# 2_PowerPerif.net
KiCad netlist of a schematic drawn in Altium Designer
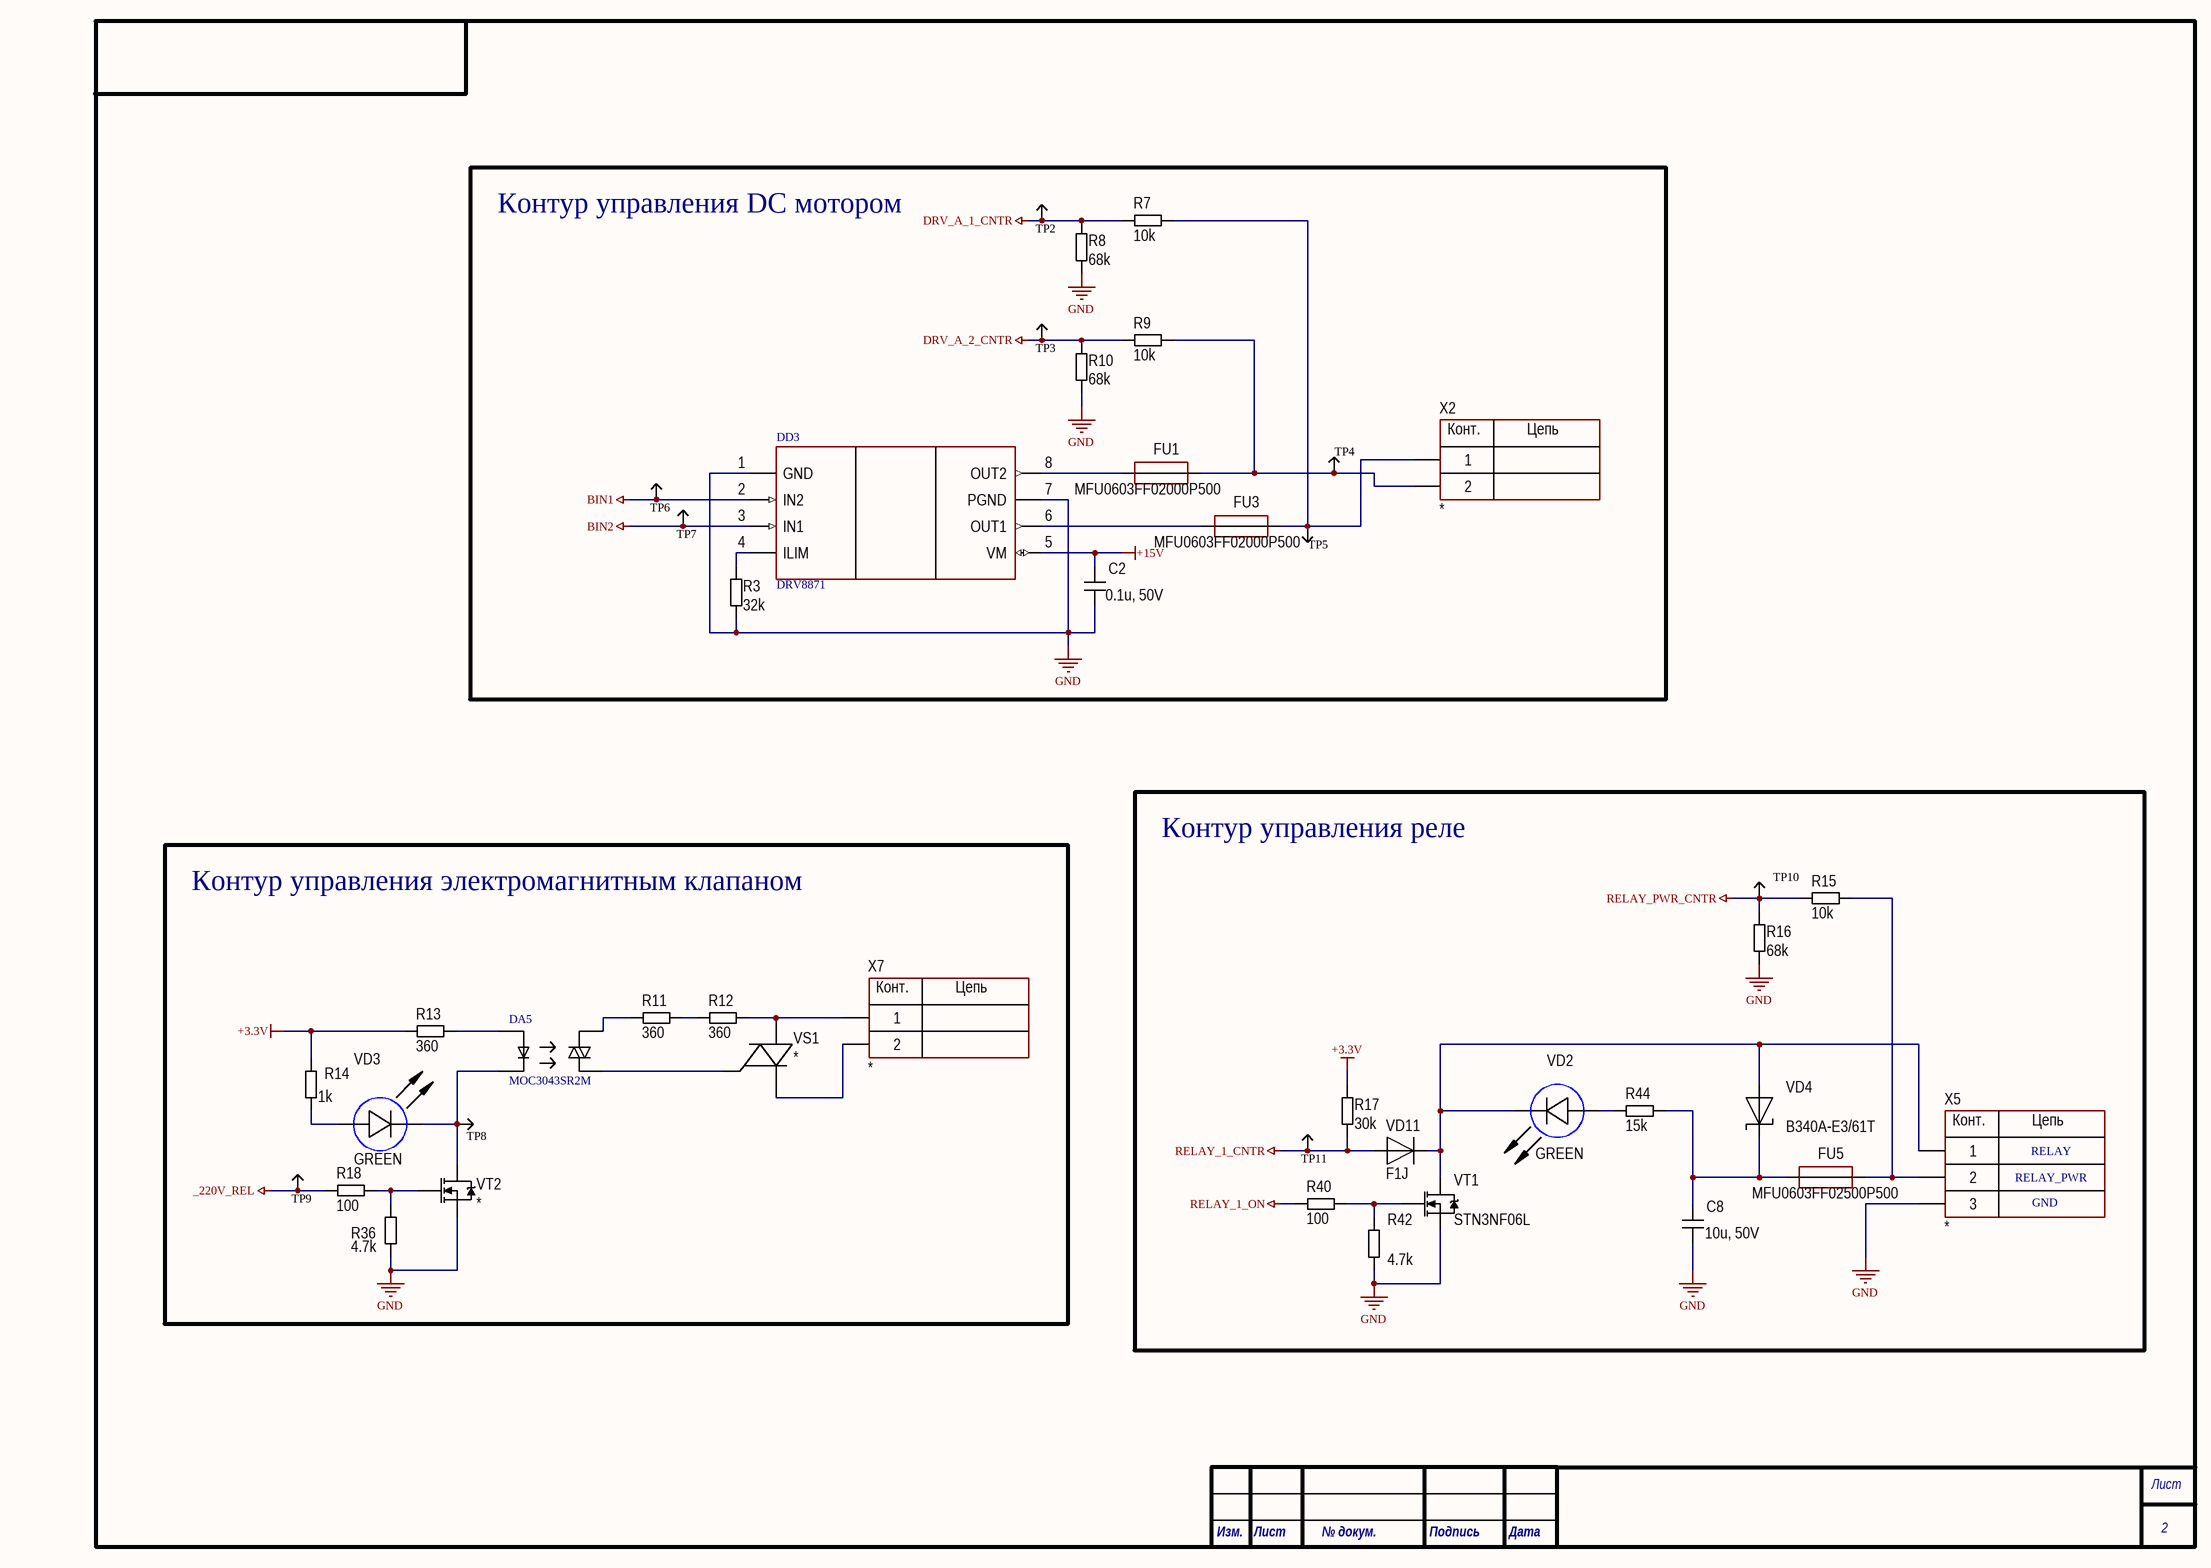
[diagram p0: 2_PowerPerif.SchDoc]

(export (version "E")
  (design (tool "Eeschema 10.0.6"))
  (components
    (comp (ref "C2")
      (value "0.1u, 50V")
      (footprint "CH0402C")
      (libsource (lib "Condensators") (part "Capacitor"))
    )
    (comp (ref "C8")
      (value "10u, 50V")
      (footprint "CH1206C")
      (libsource (lib "Condensators") (part "Capacitor"))
    )
    (comp (ref "DA5") (value "MOC3043SR2M") (footprint "DIP6") (libsource (lib "MicroIC") (part "MOC3063")))
    (comp (ref "DD3") (value "DRV8871") (footprint "8-HSOP") (libsource (lib "MicroIC") (part "DRV8871")))
    (comp (ref "FU1")
      (value "MFU0603FF02000P500")
      (footprint "CH0603F")
      (libsource (lib "Melochi") (part "Fuse"))
    )
    (comp (ref "FU3")
      (value "MFU0603FF02000P500")
      (footprint "CH0603F")
      (libsource (lib "Melochi") (part "Fuse"))
    )
    (comp (ref "FU5")
      (value "MFU0603FF02500P500")
      (footprint "CH0603F")
      (libsource (lib "Melochi") (part "Fuse"))
    )
    (comp (ref "R3") (value "32k") (footprint "CH0603R") (libsource (lib "Resistors") (part "Resistor")))
    (comp (ref "R7") (value "10k") (footprint "CH0402R") (libsource (lib "Resistors") (part "Resistor")))
    (comp (ref "R8") (value "68k") (footprint "CH0402R") (libsource (lib "Resistors") (part "Resistor")))
    (comp (ref "R9") (value "10k") (footprint "CH0402R") (libsource (lib "Resistors") (part "Resistor")))
    (comp (ref "R10") (value "68k") (footprint "CH0402R") (libsource (lib "Resistors") (part "Resistor")))
    (comp (ref "R11") (value "360") (footprint "CH1206R") (libsource (lib "Resistors") (part "Resistor")))
    (comp (ref "R12") (value "360") (footprint "CH1206R") (libsource (lib "Resistors") (part "Resistor")))
    (comp (ref "R13") (value "360") (footprint "CH0805R") (libsource (lib "Resistors") (part "Resistor")))
    (comp (ref "R14") (value "1k") (footprint "CH0805R") (libsource (lib "Resistors") (part "Resistor")))
    (comp (ref "R15") (value "10k") (footprint "CH0402R") (libsource (lib "Resistors") (part "Resistor")))
    (comp (ref "R16") (value "68k") (footprint "CH0402R") (libsource (lib "Resistors") (part "Resistor")))
    (comp (ref "R17") (value "30k") (footprint "CH0402R") (libsource (lib "Resistors") (part "Resistor")))
    (comp (ref "R18") (value "100") (footprint "CH0805R") (libsource (lib "Resistors") (part "Resistor")))
    (comp (ref "R36") (value "4.7k") (footprint "CH0402R") (libsource (lib "Resistors") (part "Resistor")))
    (comp (ref "R40") (value "100") (footprint "CH0805R") (libsource (lib "Resistors") (part "Resistor")))
    (comp (ref "R42") (value "4.7k") (footprint "CH0402R") (libsource (lib "Resistors") (part "Resistor")))
    (comp (ref "R44") (value "15k") (footprint "CH0805R") (libsource (lib "Resistors") (part "Resistor")))
    (comp (ref "TP2") (value "~") (footprint "TestPoint") (libsource (lib "Melochi") (part "TestPoint")))
    (comp (ref "TP3") (value "~") (footprint "TestPoint") (libsource (lib "Melochi") (part "TestPoint")))
    (comp (ref "TP4") (value "~") (footprint "TestPoint") (libsource (lib "Melochi") (part "TestPoint")))
    (comp (ref "TP5") (value "~") (footprint "TestPoint") (libsource (lib "Melochi") (part "TestPoint")))
    (comp (ref "TP6") (value "~") (footprint "TestPoint") (libsource (lib "Melochi") (part "TestPoint")))
    (comp (ref "TP7") (value "~") (footprint "TestPoint") (libsource (lib "Melochi") (part "TestPoint")))
    (comp (ref "TP8") (value "~") (footprint "TestPoint") (libsource (lib "Melochi") (part "TestPoint")))
    (comp (ref "TP9") (value "~") (footprint "TestPoint") (libsource (lib "Melochi") (part "TestPoint")))
    (comp (ref "TP10") (value "~") (footprint "TestPoint") (libsource (lib "Melochi") (part "TestPoint")))
    (comp (ref "TP11") (value "~") (footprint "TestPoint") (libsource (lib "Melochi") (part "TestPoint")))
    (comp (ref "VD2") (value "GREEN") (footprint "CH0603LB") (libsource (lib "Diods") (part "LED_1")))
    (comp (ref "VD3") (value "GREEN") (footprint "CH0603LB") (libsource (lib "Diods") (part "LED_1")))
    (comp (ref "VD4")
      (value "B340A-E3/61T")
      (footprint "SMA")
      (libsource (lib "Diods") (part "Diod Schottky"))
    )
    (comp (ref "VD11") (value "F1J") (footprint "SOD123F") (libsource (lib "Diods") (part "Diod")))
    (comp (ref "VS1")
      (value "*")
      (footprint "SOT223_G-D-S")
      (description "Bipolar")
      (libsource (lib "Tranzistor") (part "TRIAC"))
    )
    (comp (ref "VT1")
      (value "STN3NF06L")
      (footprint "SOT223_G-D-S")
      (description "Mosfet")
      (libsource (lib "Tranzistor") (part "N-chanel"))
    )
    (comp (ref "VT2")
      (value "*")
      (footprint "SOT23_123")
      (description "Mosfet")
      (libsource (lib "Tranzistor") (part "N-chanel"))
    )
    (comp (ref "X2")
      (value "*")
      (footprint "CON: MX-22-05-3021")
      (libsource (lib "Connectors") (part "2-Connector"))
    )
    (comp (ref "X5")
      (value "*")
      (footprint "CON: 300-03P-5.0")
      (libsource (lib "Connectors") (part "3-Connector"))
    )
    (comp (ref "X7")
      (value "*")
      (footprint "CON: 300-02P-5.0")
      (libsource (lib "Connectors") (part "2-Connector"))
    )
  )
  (nets
    (net (code "1") (name "+3.3V") (class "Default")
      (node (ref "R13") (pin "2") (pinfunction "2_2") (pintype "passive"))
      (node (ref "R14") (pin "2") (pinfunction "2_2") (pintype "passive"))
      (node (ref "R17") (pin "2") (pinfunction "2_2") (pintype "passive"))
    )
    (net (code "2") (name "+15V") (class "Default")
      (node (ref "C2") (pin "2") (pinfunction "2_2") (pintype "passive"))
      (node (ref "DD3") (pin "5") (pinfunction "VM_5") (pintype "bidirectional"))
    )
    (net (code "3") (name "BIN1") (class "Default")
      (node (ref "DD3") (pin "2") (pinfunction "IN2_2") (pintype "input"))
      (node (ref "TP6") (pin "0") (pinfunction "0_0") (pintype "passive"))
    )
    (net (code "4") (name "BIN2") (class "Default")
      (node (ref "DD3") (pin "3") (pinfunction "IN1_3") (pintype "input"))
      (node (ref "TP7") (pin "0") (pinfunction "0_0") (pintype "passive"))
    )
    (net (code "5") (name "DRV_A_1_CNTR") (class "Default")
      (node (ref "R7") (pin "1") (pinfunction "1_1") (pintype "passive"))
      (node (ref "R8") (pin "2") (pinfunction "2_2") (pintype "passive"))
      (node (ref "TP2") (pin "0") (pinfunction "0_0") (pintype "passive"))
    )
    (net (code "6") (name "DRV_A_2_CNTR") (class "Default")
      (node (ref "R10") (pin "2") (pinfunction "2_2") (pintype "passive"))
      (node (ref "R9") (pin "1") (pinfunction "1_1") (pintype "passive"))
      (node (ref "TP3") (pin "0") (pinfunction "0_0") (pintype "passive"))
    )
    (net (code "7") (name "GND") (class "Default")
      (node (ref "C2") (pin "1") (pinfunction "1_1") (pintype "passive"))
      (node (ref "C8") (pin "1") (pinfunction "1_1") (pintype "passive"))
      (node (ref "DD3") (pin "1") (pinfunction "GND_1") (pintype "power_in"))
      (node (ref "DD3") (pin "7") (pinfunction "PGND_7") (pintype "power_in"))
      (node (ref "R10") (pin "1") (pinfunction "1_1") (pintype "passive"))
      (node (ref "R16") (pin "1") (pinfunction "1_1") (pintype "passive"))
      (node (ref "R3") (pin "1") (pinfunction "1_1") (pintype "passive"))
      (node (ref "R36") (pin "1") (pinfunction "1_1") (pintype "passive"))
      (node (ref "R42") (pin "1") (pinfunction "1_1") (pintype "passive"))
      (node (ref "R8") (pin "1") (pinfunction "1_1") (pintype "passive"))
      (node (ref "VT1") (pin "3") (pinfunction "S_3") (pintype "passive"))
      (node (ref "VT2") (pin "3") (pinfunction "S_3") (pintype "passive"))
      (node (ref "X5") (pin "3") (pinfunction "3_3") (pintype "passive"))
    )
    (net (code "8") (name "Net-(C8-Pad2)") (class "Default")
      (node (ref "C8") (pin "2") (pinfunction "2_2") (pintype "passive"))
      (node (ref "FU5") (pin "1") (pinfunction "1_1") (pintype "passive"))
      (node (ref "R44") (pin "2") (pinfunction "2_2") (pintype "passive"))
      (node (ref "VD4") (pin "2") (pinfunction "2_2") (pintype "passive"))
    )
    (net (code "9") (name "Net-(DA5-Pad4)") (class "Default")
      (node (ref "DA5") (pin "4") (pinfunction "4_4") (pintype "passive"))
      (node (ref "R11") (pin "2") (pinfunction "2_2") (pintype "passive"))
    )
    (net (code "10") (name "Net-(DA5-Pad6)") (class "Default")
      (node (ref "DA5") (pin "6") (pinfunction "6_6") (pintype "passive"))
      (node (ref "VS1") (pin "3") (pinfunction "3_3") (pintype "passive"))
    )
    (net (code "11") (name "Net-(DA5-Vpr+)") (class "Default")
      (node (ref "DA5") (pin "1") (pinfunction "Vpr+_1") (pintype "passive"))
      (node (ref "R13") (pin "1") (pinfunction "1_1") (pintype "passive"))
    )
    (net (code "12") (name "Net-(DA5-Vpr-)") (class "Default")
      (node (ref "DA5") (pin "2") (pinfunction "Vpr-_2") (pintype "passive"))
      (node (ref "TP8") (pin "0") (pinfunction "0_0") (pintype "passive"))
      (node (ref "VD3") (pin "2") (pinfunction "C_2") (pintype "passive"))
      (node (ref "VT2") (pin "2") (pinfunction "D_2") (pintype "passive"))
    )
    (net (code "13") (name "Net-(DD3-ILIM)") (class "Default")
      (node (ref "DD3") (pin "4") (pinfunction "ILIM_4") (pintype "passive"))
      (node (ref "R3") (pin "2") (pinfunction "2_2") (pintype "passive"))
    )
    (net (code "14") (name "Net-(DD3-OUT1)") (class "Default")
      (node (ref "DD3") (pin "6") (pinfunction "OUT1_6") (pintype "output"))
      (node (ref "FU3") (pin "1") (pinfunction "1_1") (pintype "passive"))
    )
    (net (code "15") (name "Net-(DD3-OUT2)") (class "Default")
      (node (ref "DD3") (pin "8") (pinfunction "OUT2_8") (pintype "output"))
      (node (ref "FU1") (pin "1") (pinfunction "1_1") (pintype "passive"))
    )
    (net (code "16") (name "Net-(FU1-Pad2)") (class "Default")
      (node (ref "FU1") (pin "2") (pinfunction "2_2") (pintype "passive"))
      (node (ref "R9") (pin "2") (pinfunction "2_2") (pintype "passive"))
      (node (ref "TP4") (pin "0") (pinfunction "0_0") (pintype "passive"))
      (node (ref "X2") (pin "2") (pinfunction "2_2") (pintype "passive"))
    )
    (net (code "17") (name "Net-(FU3-Pad2)") (class "Default")
      (node (ref "FU3") (pin "2") (pinfunction "2_2") (pintype "passive"))
      (node (ref "R7") (pin "2") (pinfunction "2_2") (pintype "passive"))
      (node (ref "TP5") (pin "0") (pinfunction "0_0") (pintype "passive"))
      (node (ref "X2") (pin "1") (pinfunction "1_1") (pintype "passive"))
    )
    (net (code "18") (name "Net-(FU5-Pad2)") (class "Default")
      (node (ref "FU5") (pin "2") (pinfunction "2_2") (pintype "passive"))
      (node (ref "R15") (pin "2") (pinfunction "2_2") (pintype "passive"))
      (node (ref "X5") (pin "2") (pinfunction "2_2") (pintype "passive"))
    )
    (net (code "19") (name "Net-(R11-Pad1)") (class "Default")
      (node (ref "R11") (pin "1") (pinfunction "1_1") (pintype "passive"))
      (node (ref "R12") (pin "2") (pinfunction "2_2") (pintype "passive"))
    )
    (net (code "20") (name "Net-(R12-Pad1)") (class "Default")
      (node (ref "R12") (pin "1") (pinfunction "1_1") (pintype "passive"))
      (node (ref "VS1") (pin "2") (pinfunction "2_2") (pintype "passive"))
      (node (ref "X7") (pin "1") (pinfunction "1_1") (pintype "passive"))
    )
    (net (code "21") (name "Net-(VD2-A)") (class "Default")
      (node (ref "R44") (pin "1") (pinfunction "1_1") (pintype "passive"))
      (node (ref "VD2") (pin "1") (pinfunction "A_1") (pintype "passive"))
    )
    (net (code "22") (name "Net-(VD2-C)") (class "Default")
      (node (ref "VD11") (pin "2") (pinfunction "2_2") (pintype "passive"))
      (node (ref "VD2") (pin "2") (pinfunction "C_2") (pintype "passive"))
      (node (ref "VD4") (pin "1") (pinfunction "1_1") (pintype "passive"))
      (node (ref "VT1") (pin "2") (pinfunction "D_2") (pintype "passive"))
      (node (ref "X5") (pin "1") (pinfunction "1_1") (pintype "passive"))
    )
    (net (code "23") (name "Net-(VD3-A)") (class "Default")
      (node (ref "R14") (pin "1") (pinfunction "1_1") (pintype "passive"))
      (node (ref "VD3") (pin "1") (pinfunction "A_1") (pintype "passive"))
    )
    (net (code "24") (name "Net-(VS1-Pad1)") (class "Default")
      (node (ref "VS1") (pin "1") (pinfunction "1_1") (pintype "passive"))
      (node (ref "X7") (pin "2") (pinfunction "2_2") (pintype "passive"))
    )
    (net (code "25") (name "Net-(VT1-G)") (class "Default")
      (node (ref "R40") (pin "1") (pinfunction "1_1") (pintype "passive"))
      (node (ref "R42") (pin "2") (pinfunction "2_2") (pintype "passive"))
      (node (ref "VT1") (pin "1") (pinfunction "G_1") (pintype "passive"))
    )
    (net (code "26") (name "Net-(VT2-G)") (class "Default")
      (node (ref "R18") (pin "1") (pinfunction "1_1") (pintype "passive"))
      (node (ref "R36") (pin "2") (pinfunction "2_2") (pintype "passive"))
      (node (ref "VT2") (pin "1") (pinfunction "G_1") (pintype "passive"))
    )
    (net (code "27") (name "RELAY_1_CNTR") (class "Default")
      (node (ref "R17") (pin "1") (pinfunction "1_1") (pintype "passive"))
      (node (ref "TP11") (pin "0") (pinfunction "0_0") (pintype "passive"))
      (node (ref "VD11") (pin "1") (pinfunction "1_1") (pintype "passive"))
    )
    (net (code "28") (name "RELAY_1_ON") (class "Default")
      (node (ref "R40") (pin "2") (pinfunction "2_2") (pintype "passive"))
    )
    (net (code "29") (name "RELAY_PWR_CNTR") (class "Default")
      (node (ref "R15") (pin "1") (pinfunction "1_1") (pintype "passive"))
      (node (ref "R16") (pin "2") (pinfunction "2_2") (pintype "passive"))
      (node (ref "TP10") (pin "0") (pinfunction "0_0") (pintype "passive"))
    )
    (net (code "30") (name "_220V_REL") (class "Default")
      (node (ref "R18") (pin "2") (pinfunction "2_2") (pintype "passive"))
      (node (ref "TP9") (pin "0") (pinfunction "0_0") (pintype "passive"))
    )
  )
)
